# DualAttenuverter.net
KiCad netlist of a schematic drawn in EAGLE
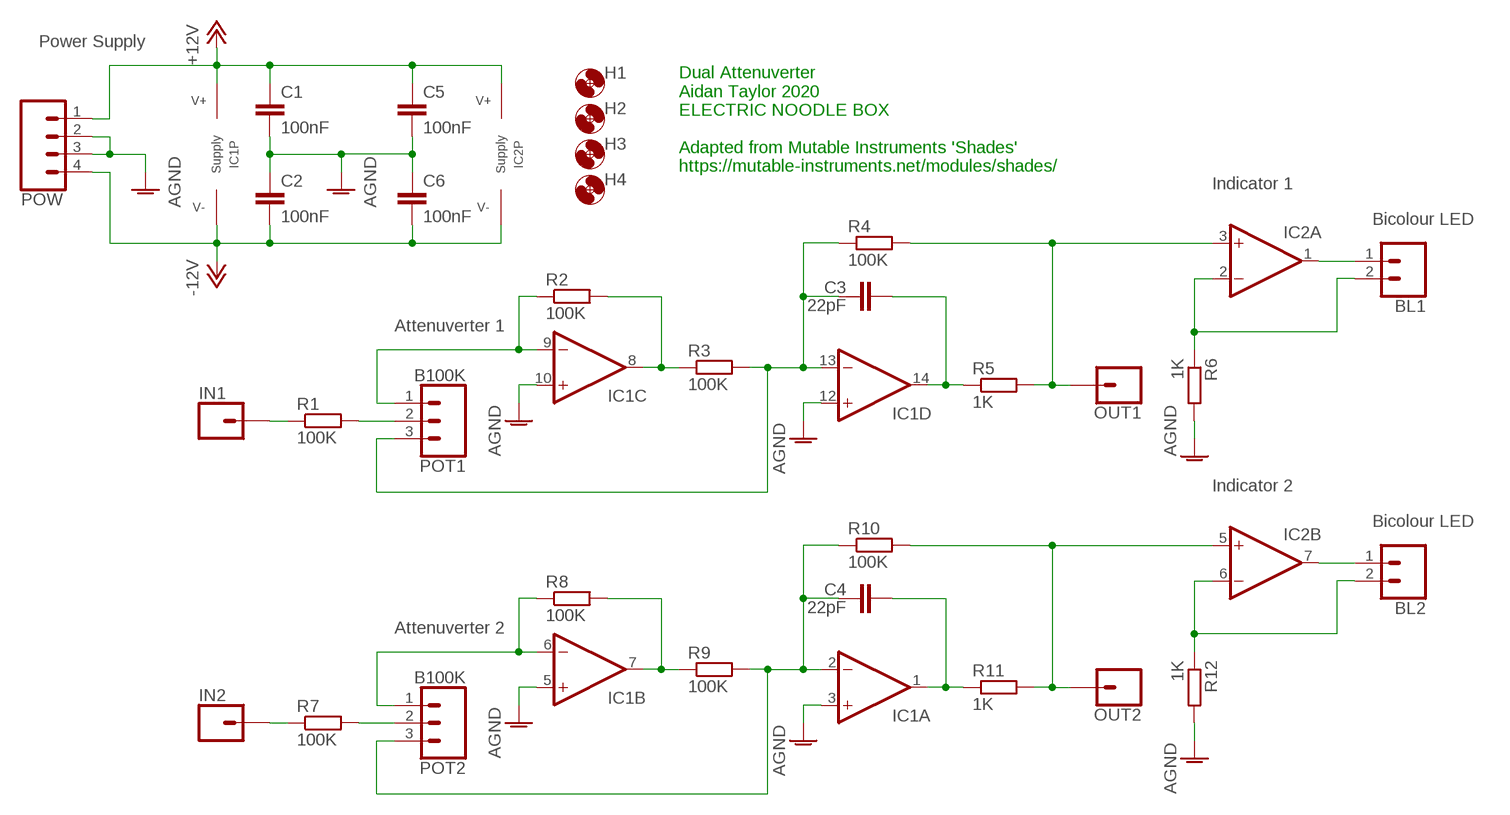
[diagram p0: schematic, sheet 1]

(export (version "E")
  (design (tool "Eeschema 10.0.6"))
  (components
    (comp (ref "BL1")
      (value "2XWIREPAD")
      (footprint "eagle-import:1X02")
      (libsource (lib "eagle-import") (part "2XWIREPAD"))
    )
    (comp (ref "BL2")
      (value "2XWIREPAD")
      (footprint "eagle-import:1X02")
      (libsource (lib "eagle-import") (part "2XWIREPAD"))
    )
    (comp (ref "C1")
      (value "100nF")
      (footprint "eagle-import:C050-025X075")
      (libsource (lib "eagle-import") (part "C-EU050-025X075"))
    )
    (comp (ref "C2")
      (value "100nF")
      (footprint "eagle-import:C050-025X075")
      (libsource (lib "eagle-import") (part "C-EU050-025X075"))
    )
    (comp (ref "C3")
      (value "22pF")
      (footprint "eagle-import:C050-025X075")
      (libsource (lib "eagle-import") (part "C-EU050-025X075"))
    )
    (comp (ref "C4")
      (value "22pF")
      (footprint "eagle-import:C050-025X075")
      (libsource (lib "eagle-import") (part "C-EU050-025X075"))
    )
    (comp (ref "C5")
      (value "100nF")
      (footprint "eagle-import:C050-025X075")
      (libsource (lib "eagle-import") (part "C-EU050-025X075"))
    )
    (comp (ref "C6")
      (value "100nF")
      (footprint "eagle-import:C050-025X075")
      (libsource (lib "eagle-import") (part "C-EU050-025X075"))
    )
    (comp (ref "H1")
      (value "MOUNT-HOLE3.2")
      (footprint "eagle-import:3,2")
      (libsource (lib "eagle-import") (part "MOUNT-HOLE3.2"))
    )
    (comp (ref "H2")
      (value "MOUNT-HOLE3.2")
      (footprint "eagle-import:3,2")
      (libsource (lib "eagle-import") (part "MOUNT-HOLE3.2"))
    )
    (comp (ref "H3")
      (value "MOUNT-HOLE3.2")
      (footprint "eagle-import:3,2")
      (libsource (lib "eagle-import") (part "MOUNT-HOLE3.2"))
    )
    (comp (ref "H4")
      (value "MOUNT-HOLE3.2")
      (footprint "eagle-import:3,2")
      (libsource (lib "eagle-import") (part "MOUNT-HOLE3.2"))
    )
    (comp (ref "IC1")
      (value "TL0X4DIL")
      (footprint "eagle-import:DIL14")
      (libsource (lib "eagle-import") (part "TL0X4DIL"))
    )
    (comp (ref "IC2")
      (value "LM358")
      (footprint "eagle-import:DIL08")
      (libsource (lib "eagle-import") (part "LM358"))
    )
    (comp (ref "IN1")
      (value "1XWIREPAD")
      (footprint "eagle-import:1X01")
      (libsource (lib "eagle-import") (part "1XWIREPAD"))
    )
    (comp (ref "IN2")
      (value "1XWIREPAD")
      (footprint "eagle-import:1X01")
      (libsource (lib "eagle-import") (part "1XWIREPAD"))
    )
    (comp (ref "OUT1")
      (value "1XWIREPAD")
      (footprint "eagle-import:1X01")
      (libsource (lib "eagle-import") (part "1XWIREPAD"))
    )
    (comp (ref "OUT2")
      (value "1XWIREPAD")
      (footprint "eagle-import:1X01")
      (libsource (lib "eagle-import") (part "1XWIREPAD"))
    )
    (comp (ref "POT1")
      (value "B100K")
      (footprint "eagle-import:1X03")
      (libsource (lib "eagle-import") (part "3XWIREPAD"))
    )
    (comp (ref "POT2")
      (value "B100K")
      (footprint "eagle-import:1X03")
      (libsource (lib "eagle-import") (part "3XWIREPAD"))
    )
    (comp (ref "POW")
      (value "4XMOLEX")
      (footprint "eagle-import:MOLEX-1X4")
      (libsource (lib "eagle-import") (part "4XMOLEX"))
    )
    (comp (ref "R1")
      (value "100K")
      (footprint "eagle-import:0207_10")
      (libsource (lib "eagle-import") (part "R-EU_0207/10"))
    )
    (comp (ref "R2")
      (value "100K")
      (footprint "eagle-import:0207_10")
      (libsource (lib "eagle-import") (part "R-EU_0207/10"))
    )
    (comp (ref "R3")
      (value "100K")
      (footprint "eagle-import:0207_10")
      (libsource (lib "eagle-import") (part "R-EU_0207/10"))
    )
    (comp (ref "R4")
      (value "100K")
      (footprint "eagle-import:0207_10")
      (libsource (lib "eagle-import") (part "R-EU_0207/10"))
    )
    (comp (ref "R5")
      (value "1K")
      (footprint "eagle-import:0207_10")
      (libsource (lib "eagle-import") (part "R-EU_0207/10"))
    )
    (comp (ref "R6")
      (value "1K")
      (footprint "eagle-import:0207_10")
      (libsource (lib "eagle-import") (part "R-EU_0207/10"))
    )
    (comp (ref "R7")
      (value "100K")
      (footprint "eagle-import:0207_10")
      (libsource (lib "eagle-import") (part "R-EU_0207/10"))
    )
    (comp (ref "R8")
      (value "100K")
      (footprint "eagle-import:0207_10")
      (libsource (lib "eagle-import") (part "R-EU_0207/10"))
    )
    (comp (ref "R9")
      (value "100K")
      (footprint "eagle-import:0207_10")
      (libsource (lib "eagle-import") (part "R-EU_0207/10"))
    )
    (comp (ref "R10")
      (value "100K")
      (footprint "eagle-import:0207_10")
      (libsource (lib "eagle-import") (part "R-EU_0207/10"))
    )
    (comp (ref "R11")
      (value "1K")
      (footprint "eagle-import:0207_10")
      (libsource (lib "eagle-import") (part "R-EU_0207/10"))
    )
    (comp (ref "R12")
      (value "1K")
      (footprint "eagle-import:0207_10")
      (libsource (lib "eagle-import") (part "R-EU_0207/10"))
    )
  )
  (nets
    (net (code "1") (name "+12V") (class "Default")
      (node (ref "C1") (pin "1") (pinfunction "1_1") (pintype "passive"))
      (node (ref "C5") (pin "1") (pinfunction "1_1") (pintype "passive"))
      (node (ref "IC1") (pin "4") (pinfunction "V+_4") (pintype "bidirectional"))
      (node (ref "IC2") (pin "8") (pinfunction "V+_8") (pintype "bidirectional"))
      (node (ref "POW") (pin "1") (pinfunction "1_1") (pintype "passive"))
    )
    (net (code "2") (name "-12V") (class "Default")
      (node (ref "C2") (pin "2") (pinfunction "2_2") (pintype "passive"))
      (node (ref "C6") (pin "2") (pinfunction "2_2") (pintype "passive"))
      (node (ref "IC1") (pin "11") (pinfunction "V-_11") (pintype "bidirectional"))
      (node (ref "IC2") (pin "4") (pinfunction "V-_4") (pintype "bidirectional"))
      (node (ref "POW") (pin "4") (pinfunction "4_4") (pintype "passive"))
    )
    (net (code "3") (name "AGND") (class "Default")
      (node (ref "C1") (pin "2") (pinfunction "2_2") (pintype "passive"))
      (node (ref "C2") (pin "1") (pinfunction "1_1") (pintype "passive"))
      (node (ref "C5") (pin "2") (pinfunction "2_2") (pintype "passive"))
      (node (ref "C6") (pin "1") (pinfunction "1_1") (pintype "passive"))
      (node (ref "IC1") (pin "10") (pinfunction "+IN_10") (pintype "input"))
      (node (ref "IC1") (pin "12") (pinfunction "+IN_12") (pintype "input"))
      (node (ref "IC1") (pin "3") (pinfunction "+IN_3") (pintype "input"))
      (node (ref "IC1") (pin "5") (pinfunction "+IN_5") (pintype "input"))
      (node (ref "POW") (pin "2") (pinfunction "2_2") (pintype "passive"))
      (node (ref "POW") (pin "3") (pinfunction "3_3") (pintype "passive"))
      (node (ref "R12") (pin "2") (pinfunction "2_2") (pintype "passive"))
      (node (ref "R6") (pin "2") (pinfunction "2_2") (pintype "passive"))
    )
    (net (code "4") (name "Net-(IC1A--IN)") (class "Default")
      (node (ref "C4") (pin "1") (pinfunction "1_1") (pintype "passive"))
      (node (ref "IC1") (pin "2") (pinfunction "-IN_2") (pintype "input"))
      (node (ref "POT2") (pin "3") (pinfunction "3_3") (pintype "passive"))
      (node (ref "R10") (pin "1") (pinfunction "1_1") (pintype "passive"))
      (node (ref "R9") (pin "2") (pinfunction "2_2") (pintype "passive"))
    )
    (net (code "5") (name "Net-(IC1A-OUT)") (class "Default")
      (node (ref "C4") (pin "2") (pinfunction "2_2") (pintype "passive"))
      (node (ref "IC1") (pin "1") (pinfunction "OUT_1") (pintype "output"))
      (node (ref "R11") (pin "1") (pinfunction "1_1") (pintype "passive"))
    )
    (net (code "6") (name "Net-(IC1B--IN)") (class "Default")
      (node (ref "IC1") (pin "6") (pinfunction "-IN_6") (pintype "input"))
      (node (ref "POT2") (pin "1") (pinfunction "1_1") (pintype "passive"))
      (node (ref "R8") (pin "1") (pinfunction "1_1") (pintype "passive"))
    )
    (net (code "7") (name "Net-(IC1B-OUT)") (class "Default")
      (node (ref "IC1") (pin "7") (pinfunction "OUT_7") (pintype "output"))
      (node (ref "R8") (pin "2") (pinfunction "2_2") (pintype "passive"))
      (node (ref "R9") (pin "1") (pinfunction "1_1") (pintype "passive"))
    )
    (net (code "8") (name "Net-(IC1C--IN)") (class "Default")
      (node (ref "IC1") (pin "9") (pinfunction "-IN_9") (pintype "input"))
      (node (ref "POT1") (pin "1") (pinfunction "1_1") (pintype "passive"))
      (node (ref "R2") (pin "1") (pinfunction "1_1") (pintype "passive"))
    )
    (net (code "9") (name "Net-(IC1C-OUT)") (class "Default")
      (node (ref "IC1") (pin "8") (pinfunction "OUT_8") (pintype "output"))
      (node (ref "R2") (pin "2") (pinfunction "2_2") (pintype "passive"))
      (node (ref "R3") (pin "1") (pinfunction "1_1") (pintype "passive"))
    )
    (net (code "10") (name "Net-(IC1D--IN)") (class "Default")
      (node (ref "C3") (pin "1") (pinfunction "1_1") (pintype "passive"))
      (node (ref "IC1") (pin "13") (pinfunction "-IN_13") (pintype "input"))
      (node (ref "POT1") (pin "3") (pinfunction "3_3") (pintype "passive"))
      (node (ref "R3") (pin "2") (pinfunction "2_2") (pintype "passive"))
      (node (ref "R4") (pin "1") (pinfunction "1_1") (pintype "passive"))
    )
    (net (code "11") (name "Net-(IC1D-OUT)") (class "Default")
      (node (ref "C3") (pin "2") (pinfunction "2_2") (pintype "passive"))
      (node (ref "IC1") (pin "14") (pinfunction "OUT_14") (pintype "output"))
      (node (ref "R5") (pin "1") (pinfunction "1_1") (pintype "passive"))
    )
    (net (code "12") (name "Net-(IC2A-+IN)") (class "Default")
      (node (ref "IC2") (pin "3") (pinfunction "+IN_3") (pintype "input"))
      (node (ref "OUT1") (pin "1") (pinfunction "1_1") (pintype "passive"))
      (node (ref "R4") (pin "2") (pinfunction "2_2") (pintype "passive"))
      (node (ref "R5") (pin "2") (pinfunction "2_2") (pintype "passive"))
    )
    (net (code "13") (name "Net-(IC2A--IN)") (class "Default")
      (node (ref "BL1") (pin "2") (pinfunction "2_2") (pintype "passive"))
      (node (ref "IC2") (pin "2") (pinfunction "-IN_2") (pintype "input"))
      (node (ref "R6") (pin "1") (pinfunction "1_1") (pintype "passive"))
    )
    (net (code "14") (name "Net-(IC2A-OUT)") (class "Default")
      (node (ref "BL1") (pin "1") (pinfunction "1_1") (pintype "passive"))
      (node (ref "IC2") (pin "1") (pinfunction "OUT_1") (pintype "output"))
    )
    (net (code "15") (name "Net-(IC2B-+IN)") (class "Default")
      (node (ref "IC2") (pin "5") (pinfunction "+IN_5") (pintype "input"))
      (node (ref "OUT2") (pin "1") (pinfunction "1_1") (pintype "passive"))
      (node (ref "R10") (pin "2") (pinfunction "2_2") (pintype "passive"))
      (node (ref "R11") (pin "2") (pinfunction "2_2") (pintype "passive"))
    )
    (net (code "16") (name "Net-(IC2B--IN)") (class "Default")
      (node (ref "BL2") (pin "2") (pinfunction "2_2") (pintype "passive"))
      (node (ref "IC2") (pin "6") (pinfunction "-IN_6") (pintype "input"))
      (node (ref "R12") (pin "1") (pinfunction "1_1") (pintype "passive"))
    )
    (net (code "17") (name "Net-(IC2B-OUT)") (class "Default")
      (node (ref "BL2") (pin "1") (pinfunction "1_1") (pintype "passive"))
      (node (ref "IC2") (pin "7") (pinfunction "OUT_7") (pintype "output"))
    )
    (net (code "18") (name "Net-(IN1-Pad1)") (class "Default")
      (node (ref "IN1") (pin "1") (pinfunction "1_1") (pintype "passive"))
      (node (ref "R1") (pin "1") (pinfunction "1_1") (pintype "passive"))
    )
    (net (code "19") (name "Net-(IN2-Pad1)") (class "Default")
      (node (ref "IN2") (pin "1") (pinfunction "1_1") (pintype "passive"))
      (node (ref "R7") (pin "1") (pinfunction "1_1") (pintype "passive"))
    )
    (net (code "20") (name "Net-(POT1-Pad2)") (class "Default")
      (node (ref "POT1") (pin "2") (pinfunction "2_2") (pintype "passive"))
      (node (ref "R1") (pin "2") (pinfunction "2_2") (pintype "passive"))
    )
    (net (code "21") (name "Net-(POT2-Pad2)") (class "Default")
      (node (ref "POT2") (pin "2") (pinfunction "2_2") (pintype "passive"))
      (node (ref "R7") (pin "2") (pinfunction "2_2") (pintype "passive"))
    )
  )
)
